# UCirKitUserStudy4-3.net
KiCad netlist of a schematic drawn in EAGLE
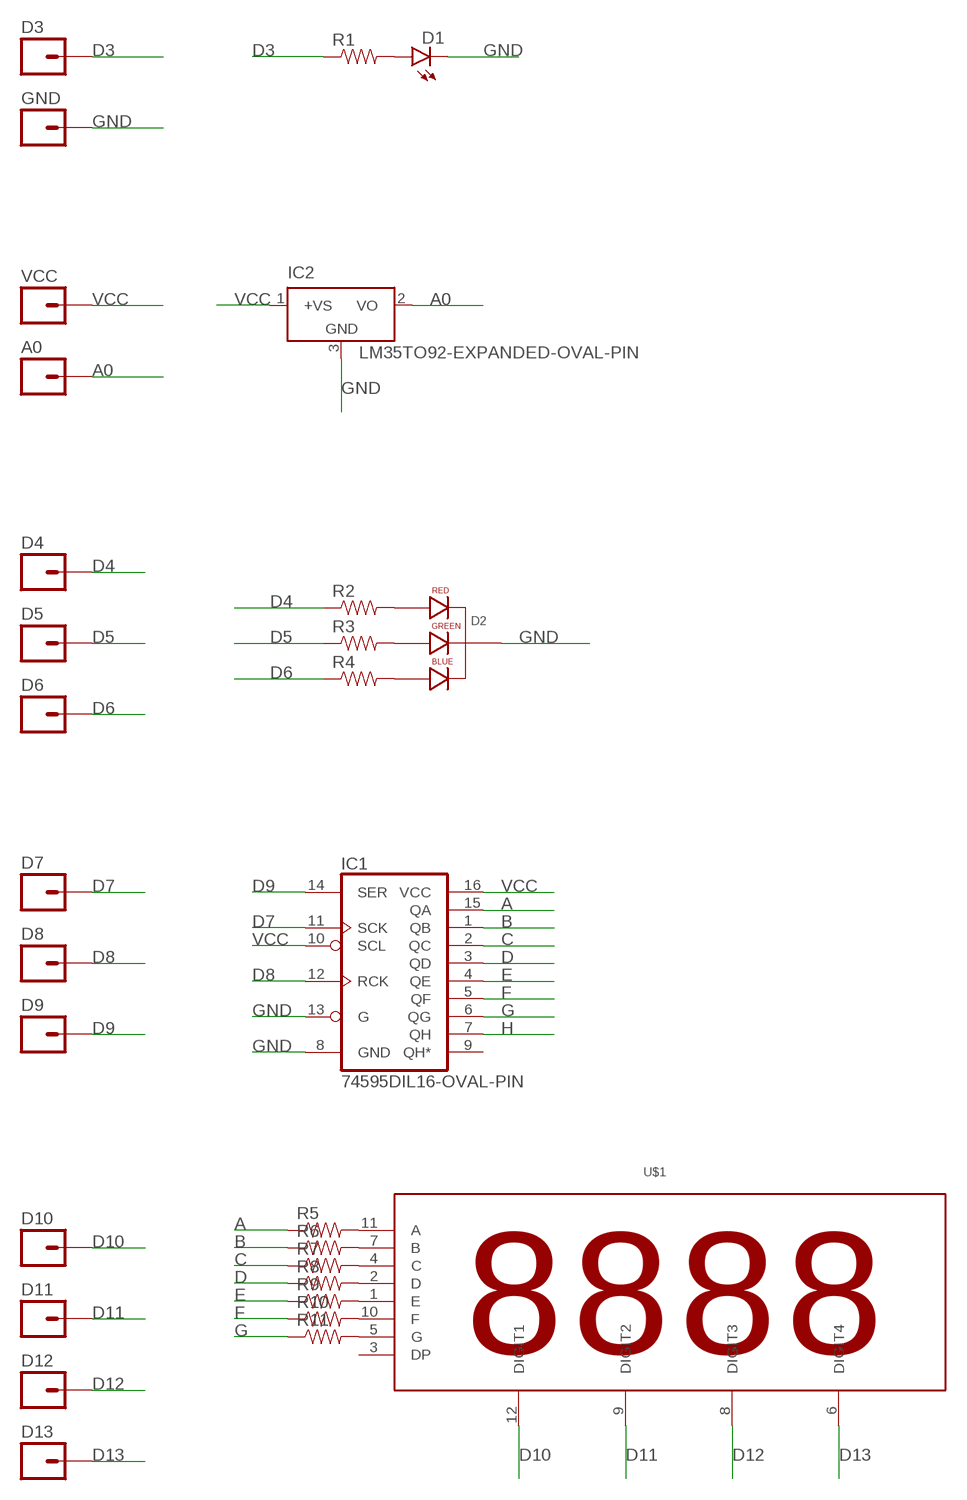
[diagram p0: schematic, sheet 1]

(export (version "E")
  (design (tool "Eeschema 10.0.6"))
  (components
    (comp (ref "A0")
      (value "M01OVAL_PIN")
      (footprint "eagle-import:1X01_OVAL_PIN")
      (libsource (lib "eagle-import") (part "M01OVAL_PIN"))
    )
    (comp (ref "D1")
      (value "LEDLED3MM-EXPANDED-OVAL-PIN")
      (footprint "eagle-import:LED3MM-EXPANDED-OVAL-PIN")
      (libsource (lib "eagle-import") (part "LEDLED3MM-EXPANDED-OVAL-PIN"))
    )
    (comp (ref "D2")
      (value "LED-RGB-CC-THRULED-RGB-THRU-EXPANDED-OVAL-PIN")
      (footprint "eagle-import:LED-RGB-THRU-EXPANDED-OVAL-PIN")
      (libsource (lib "eagle-import") (part "LED-RGB-CC-THRULED-RGB-THRU-EXPANDED-OVAL-PIN"))
    )
    (comp (ref "D3")
      (value "M01OVAL_PIN")
      (footprint "eagle-import:1X01_OVAL_PIN")
      (libsource (lib "eagle-import") (part "M01OVAL_PIN"))
    )
    (comp (ref "D4")
      (value "M01OVAL_PIN")
      (footprint "eagle-import:1X01_OVAL_PIN")
      (libsource (lib "eagle-import") (part "M01OVAL_PIN"))
    )
    (comp (ref "D5")
      (value "M01OVAL_PIN")
      (footprint "eagle-import:1X01_OVAL_PIN")
      (libsource (lib "eagle-import") (part "M01OVAL_PIN"))
    )
    (comp (ref "D6")
      (value "M01OVAL_PIN")
      (footprint "eagle-import:1X01_OVAL_PIN")
      (libsource (lib "eagle-import") (part "M01OVAL_PIN"))
    )
    (comp (ref "D7")
      (value "M01OVAL_PIN")
      (footprint "eagle-import:1X01_OVAL_PIN")
      (libsource (lib "eagle-import") (part "M01OVAL_PIN"))
    )
    (comp (ref "D8")
      (value "M01OVAL_PIN")
      (footprint "eagle-import:1X01_OVAL_PIN")
      (libsource (lib "eagle-import") (part "M01OVAL_PIN"))
    )
    (comp (ref "D9")
      (value "M01OVAL_PIN")
      (footprint "eagle-import:1X01_OVAL_PIN")
      (libsource (lib "eagle-import") (part "M01OVAL_PIN"))
    )
    (comp (ref "D10")
      (value "M01OVAL_PIN")
      (footprint "eagle-import:1X01_OVAL_PIN")
      (libsource (lib "eagle-import") (part "M01OVAL_PIN"))
    )
    (comp (ref "D11")
      (value "M01OVAL_PIN")
      (footprint "eagle-import:1X01_OVAL_PIN")
      (libsource (lib "eagle-import") (part "M01OVAL_PIN"))
    )
    (comp (ref "D12")
      (value "M01OVAL_PIN")
      (footprint "eagle-import:1X01_OVAL_PIN")
      (libsource (lib "eagle-import") (part "M01OVAL_PIN"))
    )
    (comp (ref "D13")
      (value "M01OVAL_PIN")
      (footprint "eagle-import:1X01_OVAL_PIN")
      (libsource (lib "eagle-import") (part "M01OVAL_PIN"))
    )
    (comp (ref "GND")
      (value "M01OVAL_PIN")
      (footprint "eagle-import:1X01_OVAL_PIN")
      (libsource (lib "eagle-import") (part "M01OVAL_PIN"))
    )
    (comp (ref "IC1")
      (value "74595DIL16-OVAL-PIN")
      (footprint "eagle-import:DIL16-OVAL-PIN")
      (libsource (lib "eagle-import") (part "74595DIL16-OVAL-PIN"))
    )
    (comp (ref "IC2")
      (value "LM35TO92-EXPANDED-OVAL-PIN")
      (footprint "eagle-import:TO92-EXPANDED-OVAL-PIN")
      (libsource (lib "eagle-import") (part "LM35TO92-EXPANDED-OVAL-PIN"))
    )
    (comp (ref "R1")
      (value "1KOHM-1/4W-1%(PTH)PTH-EXPANDED-OVAL-PIN")
      (footprint "eagle-import:PTH-EXPANDED-OVAL-PIN")
      (libsource (lib "eagle-import") (part "1KOHM-1/4W-1%(PTH)PTH-EXPANDED-OVAL-PIN"))
    )
    (comp (ref "R2")
      (value "1KOHM-1/4W-1%(PTH)PTH-EXPANDED-OVAL-PIN")
      (footprint "eagle-import:PTH-EXPANDED-OVAL-PIN")
      (libsource (lib "eagle-import") (part "1KOHM-1/4W-1%(PTH)PTH-EXPANDED-OVAL-PIN"))
    )
    (comp (ref "R3")
      (value "1KOHM-1/4W-1%(PTH)PTH-EXPANDED-OVAL-PIN")
      (footprint "eagle-import:PTH-EXPANDED-OVAL-PIN")
      (libsource (lib "eagle-import") (part "1KOHM-1/4W-1%(PTH)PTH-EXPANDED-OVAL-PIN"))
    )
    (comp (ref "R4")
      (value "1KOHM-1/4W-1%(PTH)PTH-EXPANDED-OVAL-PIN")
      (footprint "eagle-import:PTH-EXPANDED-OVAL-PIN")
      (libsource (lib "eagle-import") (part "1KOHM-1/4W-1%(PTH)PTH-EXPANDED-OVAL-PIN"))
    )
    (comp (ref "R5")
      (value "1KOHM-1/4W-1%(PTH)PTH-EXPANDED-OVAL-PIN")
      (footprint "eagle-import:PTH-EXPANDED-OVAL-PIN")
      (libsource (lib "eagle-import") (part "1KOHM-1/4W-1%(PTH)PTH-EXPANDED-OVAL-PIN"))
    )
    (comp (ref "R6")
      (value "1KOHM-1/4W-1%(PTH)PTH-EXPANDED-OVAL-PIN")
      (footprint "eagle-import:PTH-EXPANDED-OVAL-PIN")
      (libsource (lib "eagle-import") (part "1KOHM-1/4W-1%(PTH)PTH-EXPANDED-OVAL-PIN"))
    )
    (comp (ref "R7")
      (value "1KOHM-1/4W-1%(PTH)PTH-EXPANDED-OVAL-PIN")
      (footprint "eagle-import:PTH-EXPANDED-OVAL-PIN")
      (libsource (lib "eagle-import") (part "1KOHM-1/4W-1%(PTH)PTH-EXPANDED-OVAL-PIN"))
    )
    (comp (ref "R8")
      (value "1KOHM-1/4W-1%(PTH)PTH-EXPANDED-OVAL-PIN")
      (footprint "eagle-import:PTH-EXPANDED-OVAL-PIN")
      (libsource (lib "eagle-import") (part "1KOHM-1/4W-1%(PTH)PTH-EXPANDED-OVAL-PIN"))
    )
    (comp (ref "R9")
      (value "1KOHM-1/4W-1%(PTH)PTH-EXPANDED-OVAL-PIN")
      (footprint "eagle-import:PTH-EXPANDED-OVAL-PIN")
      (libsource (lib "eagle-import") (part "1KOHM-1/4W-1%(PTH)PTH-EXPANDED-OVAL-PIN"))
    )
    (comp (ref "R10")
      (value "1KOHM-1/4W-1%(PTH)PTH-EXPANDED-OVAL-PIN")
      (footprint "eagle-import:PTH-EXPANDED-OVAL-PIN")
      (libsource (lib "eagle-import") (part "1KOHM-1/4W-1%(PTH)PTH-EXPANDED-OVAL-PIN"))
    )
    (comp (ref "R11")
      (value "1KOHM-1/4W-1%(PTH)PTH-EXPANDED-OVAL-PIN")
      (footprint "eagle-import:PTH-EXPANDED-OVAL-PIN")
      (libsource (lib "eagle-import") (part "1KOHM-1/4W-1%(PTH)PTH-EXPANDED-OVAL-PIN"))
    )
    (comp (ref "U$1")
      (value "4DIGIT_SEVEN_SEGMENT4DIGIT_SEVEN_SEGMENT_OVAL_PIN")
      (footprint "eagle-import:4DIGIT_SEVEN_SEGMENT_OVAL_PIN")
      (libsource (lib "eagle-import") (part "4DIGIT_SEVEN_SEGMENT4DIGIT_SEVEN_SEGMENT_OVAL_PIN"))
    )
    (comp (ref "VCC")
      (value "M01OVAL_PIN")
      (footprint "eagle-import:1X01_OVAL_PIN")
      (libsource (lib "eagle-import") (part "M01OVAL_PIN"))
    )
  )
  (nets
    (net (code "1") (name "/A") (class "Default")
      (node (ref "IC1") (pin "15") (pinfunction "QA_15") (pintype "tri_state"))
      (node (ref "R5") (pin "P$1") (pinfunction "1_P$1") (pintype "passive"))
    )
    (net (code "2") (name "/A0") (class "Default")
      (node (ref "A0") (pin "1") (pinfunction "1_1") (pintype "passive"))
      (node (ref "IC2") (pin "2") (pinfunction "VO_2") (pintype "input"))
    )
    (net (code "3") (name "/B") (class "Default")
      (node (ref "IC1") (pin "1") (pinfunction "QB_1") (pintype "tri_state"))
      (node (ref "R6") (pin "P$1") (pinfunction "1_P$1") (pintype "passive"))
    )
    (net (code "4") (name "/C") (class "Default")
      (node (ref "IC1") (pin "2") (pinfunction "QC_2") (pintype "tri_state"))
      (node (ref "R7") (pin "P$1") (pinfunction "1_P$1") (pintype "passive"))
    )
    (net (code "5") (name "/D") (class "Default")
      (node (ref "IC1") (pin "3") (pinfunction "QD_3") (pintype "tri_state"))
      (node (ref "R8") (pin "P$1") (pinfunction "1_P$1") (pintype "passive"))
    )
    (net (code "6") (name "/D3") (class "Default")
      (node (ref "D3") (pin "1") (pinfunction "1_1") (pintype "passive"))
      (node (ref "R1") (pin "P$1") (pinfunction "1_P$1") (pintype "passive"))
    )
    (net (code "7") (name "/D4") (class "Default")
      (node (ref "D4") (pin "1") (pinfunction "1_1") (pintype "passive"))
      (node (ref "R2") (pin "P$1") (pinfunction "1_P$1") (pintype "passive"))
    )
    (net (code "8") (name "/D5") (class "Default")
      (node (ref "D5") (pin "1") (pinfunction "1_1") (pintype "passive"))
      (node (ref "R3") (pin "P$1") (pinfunction "1_P$1") (pintype "passive"))
    )
    (net (code "9") (name "/D6") (class "Default")
      (node (ref "D6") (pin "1") (pinfunction "1_1") (pintype "passive"))
      (node (ref "R4") (pin "P$1") (pinfunction "1_P$1") (pintype "passive"))
    )
    (net (code "10") (name "/D7") (class "Default")
      (node (ref "D7") (pin "1") (pinfunction "1_1") (pintype "passive"))
      (node (ref "IC1") (pin "11") (pinfunction "SCK_11") (pintype "input"))
    )
    (net (code "11") (name "/D8") (class "Default")
      (node (ref "D8") (pin "1") (pinfunction "1_1") (pintype "passive"))
      (node (ref "IC1") (pin "12") (pinfunction "RCK_12") (pintype "input"))
    )
    (net (code "12") (name "/D9") (class "Default")
      (node (ref "D9") (pin "1") (pinfunction "1_1") (pintype "passive"))
      (node (ref "IC1") (pin "14") (pinfunction "SER_14") (pintype "input"))
    )
    (net (code "13") (name "/D10") (class "Default")
      (node (ref "D10") (pin "1") (pinfunction "1_1") (pintype "passive"))
      (node (ref "U$1") (pin "12") (pinfunction "DIGIT1_12") (pintype "bidirectional"))
    )
    (net (code "14") (name "/D11") (class "Default")
      (node (ref "D11") (pin "1") (pinfunction "1_1") (pintype "passive"))
      (node (ref "U$1") (pin "9") (pinfunction "DIGIT2_9") (pintype "bidirectional"))
    )
    (net (code "15") (name "/D12") (class "Default")
      (node (ref "D12") (pin "1") (pinfunction "1_1") (pintype "passive"))
      (node (ref "U$1") (pin "8") (pinfunction "DIGIT3_8") (pintype "bidirectional"))
    )
    (net (code "16") (name "/D13") (class "Default")
      (node (ref "D13") (pin "1") (pinfunction "1_1") (pintype "passive"))
      (node (ref "U$1") (pin "6") (pinfunction "DIGIT4_6") (pintype "bidirectional"))
    )
    (net (code "17") (name "/E") (class "Default")
      (node (ref "IC1") (pin "4") (pinfunction "QE_4") (pintype "tri_state"))
      (node (ref "R9") (pin "P$1") (pinfunction "1_P$1") (pintype "passive"))
    )
    (net (code "18") (name "/F") (class "Default")
      (node (ref "IC1") (pin "5") (pinfunction "QF_5") (pintype "tri_state"))
      (node (ref "R10") (pin "P$1") (pinfunction "1_P$1") (pintype "passive"))
    )
    (net (code "19") (name "/G") (class "Default")
      (node (ref "IC1") (pin "6") (pinfunction "QG_6") (pintype "tri_state"))
      (node (ref "R11") (pin "P$1") (pinfunction "1_P$1") (pintype "passive"))
    )
    (net (code "20") (name "/GND") (class "Default")
      (node (ref "D1") (pin "K") (pinfunction "C_K") (pintype "passive"))
      (node (ref "D2") (pin "2") (pinfunction "CATHODE_2") (pintype "bidirectional"))
      (node (ref "GND") (pin "1") (pinfunction "1_1") (pintype "passive"))
      (node (ref "IC1") (pin "13") (pinfunction "G_13") (pintype "input"))
      (node (ref "IC1") (pin "8") (pinfunction "GND_8") (pintype "power_in"))
      (node (ref "IC2") (pin "3") (pinfunction "GND_3") (pintype "power_in"))
    )
    (net (code "21") (name "/H") (class "Default")
      (node (ref "IC1") (pin "7") (pinfunction "QH_7") (pintype "tri_state"))
    )
    (net (code "22") (name "/VCC") (class "Default")
      (node (ref "IC1") (pin "10") (pinfunction "SCL_10") (pintype "input"))
      (node (ref "IC1") (pin "16") (pinfunction "VCC_16") (pintype "power_in"))
      (node (ref "IC2") (pin "1") (pinfunction "+VS_1") (pintype "input"))
      (node (ref "VCC") (pin "1") (pinfunction "1_1") (pintype "passive"))
    )
    (net (code "23") (name "Net-(D2-BLUE_CATHODE)") (class "Default")
      (node (ref "D2") (pin "4") (pinfunction "BLUE_CATHODE_4") (pintype "bidirectional"))
      (node (ref "R4") (pin "P$2") (pinfunction "2_P$2") (pintype "passive"))
    )
    (net (code "24") (name "Net-(D2-GREEN_CATHODE)") (class "Default")
      (node (ref "D2") (pin "3") (pinfunction "GREEN_CATHODE_3") (pintype "bidirectional"))
      (node (ref "R3") (pin "P$2") (pinfunction "2_P$2") (pintype "passive"))
    )
    (net (code "25") (name "Net-(D2-RED_CATHODE)") (class "Default")
      (node (ref "D2") (pin "1") (pinfunction "RED_CATHODE_1") (pintype "bidirectional"))
      (node (ref "R2") (pin "P$2") (pinfunction "2_P$2") (pintype "passive"))
    )
    (net (code "26") (name "Net-(R1-2)") (class "Default")
      (node (ref "D1") (pin "A") (pinfunction "A_A") (pintype "passive"))
      (node (ref "R1") (pin "P$2") (pinfunction "2_P$2") (pintype "passive"))
    )
    (net (code "27") (name "Net-(R5-2)") (class "Default")
      (node (ref "R5") (pin "P$2") (pinfunction "2_P$2") (pintype "passive"))
      (node (ref "U$1") (pin "11") (pinfunction "A_11") (pintype "bidirectional"))
    )
    (net (code "28") (name "Net-(R6-2)") (class "Default")
      (node (ref "R6") (pin "P$2") (pinfunction "2_P$2") (pintype "passive"))
      (node (ref "U$1") (pin "7") (pinfunction "B_7") (pintype "bidirectional"))
    )
    (net (code "29") (name "Net-(R7-2)") (class "Default")
      (node (ref "R7") (pin "P$2") (pinfunction "2_P$2") (pintype "passive"))
      (node (ref "U$1") (pin "4") (pinfunction "C_4") (pintype "bidirectional"))
    )
    (net (code "30") (name "Net-(R8-2)") (class "Default")
      (node (ref "R8") (pin "P$2") (pinfunction "2_P$2") (pintype "passive"))
      (node (ref "U$1") (pin "2") (pinfunction "D_2") (pintype "bidirectional"))
    )
    (net (code "31") (name "Net-(R9-2)") (class "Default")
      (node (ref "R9") (pin "P$2") (pinfunction "2_P$2") (pintype "passive"))
      (node (ref "U$1") (pin "1") (pinfunction "E_1") (pintype "bidirectional"))
    )
    (net (code "32") (name "Net-(R10-2)") (class "Default")
      (node (ref "R10") (pin "P$2") (pinfunction "2_P$2") (pintype "passive"))
      (node (ref "U$1") (pin "10") (pinfunction "F_10") (pintype "bidirectional"))
    )
    (net (code "33") (name "Net-(R11-2)") (class "Default")
      (node (ref "R11") (pin "P$2") (pinfunction "2_P$2") (pintype "passive"))
      (node (ref "U$1") (pin "5") (pinfunction "G_5") (pintype "bidirectional"))
    )
    (net (code "34") (name "unconnected-(IC1-QH*-Pad9)") (class "Default")
      (node (ref "IC1") (pin "9") (pinfunction "QH*_9") (pintype "tri_state"))
    )
    (net (code "35") (name "unconnected-(U$1-DP-Pad3)") (class "Default")
      (node (ref "U$1") (pin "3") (pinfunction "DP_3") (pintype "bidirectional"))
    )
  )
)
